# MCU.net
KiCad netlist of a schematic drawn in Altium Designer
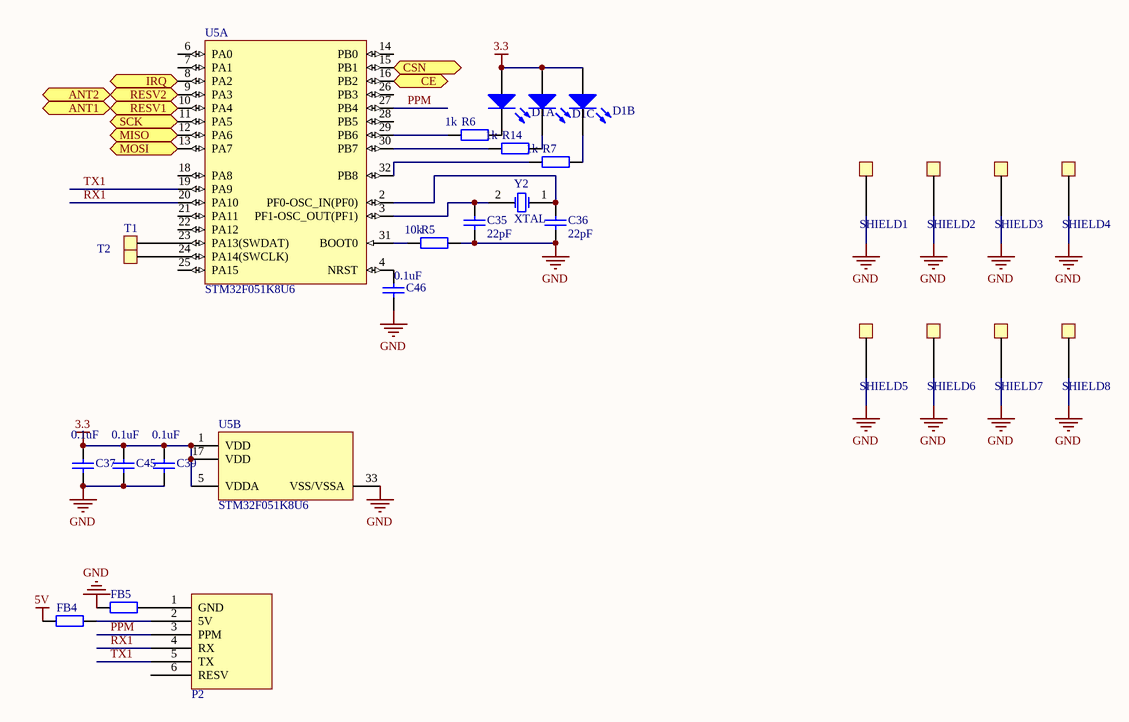
[diagram p0: MCU.SchDoc]

(export (version "E")
  (design (tool "Eeschema 10.0.6"))
  (components
    (comp (ref "C35")
      (value "22pF")
      (footprint "0402")
      (description "Capacitor")
      (fields (field (name "PUBLISHER") "Altium Limited"))
      (libsource (lib "RTC6705") (part "Cap"))
    )
    (comp (ref "C36")
      (value "22pF")
      (footprint "0402")
      (description "Capacitor")
      (fields (field (name "PUBLISHER") "Altium Limited"))
      (libsource (lib "RTC6705") (part "Cap"))
    )
    (comp (ref "C37")
      (value "0.1uF")
      (footprint "0402")
      (description "Capacitor")
      (fields (field (name "PUBLISHER") "Altium Limited"))
      (libsource (lib "RTC6705") (part "Cap"))
    )
    (comp (ref "C39")
      (value "0.1uF")
      (footprint "0402")
      (description "Capacitor")
      (fields (field (name "PUBLISHER") "Altium Limited"))
      (libsource (lib "RTC6705") (part "Cap"))
    )
    (comp (ref "C45")
      (value "0.1uF")
      (footprint "0402")
      (description "Capacitor")
      (fields (field (name "PUBLISHER") "Altium Limited"))
      (libsource (lib "RTC6705") (part "Cap"))
    )
    (comp (ref "C46")
      (value "0.1uF")
      (footprint "0402")
      (description "Capacitor")
      (fields (field (name "PUBLISHER") "Altium Limited"))
      (libsource (lib "RTC6705") (part "Cap"))
    )
    (comp (ref "D1")
      (value "LEDx3")
      (footprint "LC-0603_Rx2")
      (description "Typical RED GaAs LED")
      (fields (field (name "PUBLISHER") "Altium Limited"))
      (libsource (lib "sch") (part "LEDx3"))
    )
    (comp (ref "FB4")
      (value "Res2")
      (footprint "0402")
      (description "Resistor")
      (fields (field (name "PUBLISHER") "Altium Limited"))
      (libsource (lib "RTC6705") (part "Res2"))
    )
    (comp (ref "FB5")
      (value "Res2")
      (footprint "0402")
      (description "Resistor")
      (fields (field (name "PUBLISHER") "Altium Limited"))
      (libsource (lib "RTC6705") (part "Res2"))
    )
    (comp (ref "P2") (value "PPMInf") (footprint "PPMInf") (libsource (lib "NRF24L01_PA") (part "PPMInf")))
    (comp (ref "R5")
      (value "10k")
      (footprint "0402")
      (description "Resistor")
      (fields (field (name "PUBLISHER") "Altium Limited"))
      (libsource (lib "RTC6705") (part "Res2"))
    )
    (comp (ref "R6")
      (value "1k")
      (footprint "0402")
      (description "Resistor")
      (fields (field (name "PUBLISHER") "Altium Limited"))
      (libsource (lib "RTC6705") (part "Res2"))
    )
    (comp (ref "R7")
      (value "1k")
      (footprint "0402")
      (description "Resistor")
      (fields (field (name "PUBLISHER") "Altium Limited"))
      (libsource (lib "RTC6705") (part "Res2"))
    )
    (comp (ref "R14")
      (value "1k")
      (footprint "0402")
      (description "Resistor")
      (fields (field (name "PUBLISHER") "Altium Limited"))
      (libsource (lib "RTC6705") (part "Res2"))
    )
    (comp (ref "SHIELD1")
      (value "D")
      (footprint "ShieldHolder_6.5*0.8")
      (libsource (lib "") (part "TestPad_1"))
    )
    (comp (ref "SHIELD2")
      (value "D")
      (footprint "ShieldHolder_6.5*0.8")
      (libsource (lib "") (part "TestPad_1"))
    )
    (comp (ref "SHIELD3")
      (value "D")
      (footprint "ShieldHolder_6.5*0.8")
      (libsource (lib "") (part "TestPad_1"))
    )
    (comp (ref "SHIELD4")
      (value "D")
      (footprint "ShieldHolder_6.5*0.8")
      (libsource (lib "") (part "TestPad_1"))
    )
    (comp (ref "SHIELD5")
      (value "D")
      (footprint "ShieldHolder_6.5*0.8")
      (libsource (lib "") (part "TestPad_1"))
    )
    (comp (ref "SHIELD6")
      (value "D")
      (footprint "ShieldHolder_6.5*0.8")
      (libsource (lib "") (part "TestPad_1"))
    )
    (comp (ref "SHIELD7")
      (value "D")
      (footprint "ShieldHolder_6.5*0.8")
      (libsource (lib "") (part "TestPad_1"))
    )
    (comp (ref "SHIELD8")
      (value "D")
      (footprint "ShieldHolder_6.5*0.8")
      (libsource (lib "") (part "TestPad_1"))
    )
    (comp (ref "T1") (value "D") (footprint "TestPad - 1mm") (libsource (lib "sch") (part "TestPad")))
    (comp (ref "T2") (value "TestPad") (footprint "TestPad - 1mm") (libsource (lib "sch") (part "TestPad")))
    (comp (ref "U5")
      (value "STM32F051K8U6")
      (footprint "STM-UFQFPN32_NX")
      (libsource (lib "STMicroelectronics STM32 F0") (part "STM32F051K8U6"))
    )
    (comp (ref "Y2")
      (value "XTAL")
      (footprint "OSCILLATOR-3.2X2.5 - 2P")
      (description "Crystal Oscillator")
      (fields (field (name "PUBLISHER") "Altium Limited"))
      (libsource (lib "Miscellaneous Devices") (part "XTAL"))
    )
  )
  (nets
    (net (code "5") (name "/CE") (class "Default")
      (node (ref "U5") (pin "16") (pinfunction "PB2_16") (pintype "bidirectional"))
    )
    (net (code "6") (name "/CSN") (class "Default")
      (node (ref "U5") (pin "15") (pinfunction "PB1_15") (pintype "bidirectional"))
    )
    (net (code "7") (name "/IRQ") (class "Default")
      (node (ref "U5") (pin "8") (pinfunction "PA2_8") (pintype "bidirectional"))
    )
    (net (code "8") (name "/MISO") (class "Default")
      (node (ref "U5") (pin "12") (pinfunction "PA6_12") (pintype "bidirectional"))
    )
    (net (code "9") (name "/MOSI") (class "Default")
      (node (ref "U5") (pin "13") (pinfunction "PA7_13") (pintype "bidirectional"))
    )
    (net (code "10") (name "/PPM") (class "Default")
      (node (ref "P2") (pin "3") (pinfunction "PPM_3") (pintype "passive"))
      (node (ref "U5") (pin "27") (pinfunction "PB4_27") (pintype "bidirectional"))
    )
    (net (code "11") (name "/RESV1") (class "Default")
      (node (ref "U5") (pin "10") (pinfunction "PA4_10") (pintype "bidirectional"))
    )
    (net (code "12") (name "/RESV2") (class "Default")
      (node (ref "U5") (pin "9") (pinfunction "PA3_9") (pintype "bidirectional"))
    )
    (net (code "13") (name "/RX1") (class "Default")
      (node (ref "P2") (pin "4") (pinfunction "RX_4") (pintype "passive"))
      (node (ref "U5") (pin "20") (pinfunction "PA10_20") (pintype "bidirectional"))
    )
    (net (code "14") (name "/SCK") (class "Default")
      (node (ref "U5") (pin "11") (pinfunction "PA5_11") (pintype "bidirectional"))
    )
    (net (code "15") (name "/TX1") (class "Default")
      (node (ref "P2") (pin "5") (pinfunction "TX_5") (pintype "passive"))
      (node (ref "U5") (pin "19") (pinfunction "PA9_19") (pintype "bidirectional"))
    )
    (net (code "16") (name "3.3") (class "Default")
      (node (ref "C37") (pin "1") (pinfunction "1_1") (pintype "passive"))
      (node (ref "C39") (pin "1") (pinfunction "1_1") (pintype "passive"))
      (node (ref "C45") (pin "1") (pinfunction "1_1") (pintype "passive"))
      (node (ref "D1") (pin "2") (pinfunction "A_2") (pintype "passive"))
      (node (ref "U5") (pin "1") (pinfunction "VDD_1") (pintype "power_in"))
      (node (ref "U5") (pin "17") (pinfunction "VDD_17") (pintype "power_in"))
      (node (ref "U5") (pin "5") (pinfunction "VDDA_5") (pintype "power_in"))
    )
    (net (code "17") (name "5V") (class "Default")
      (node (ref "FB4") (pin "1") (pinfunction "1_1") (pintype "passive"))
    )
    (net (code "18") (name "GND") (class "Default")
      (node (ref "C35") (pin "2") (pinfunction "2_2") (pintype "passive"))
      (node (ref "C36") (pin "1") (pinfunction "1_1") (pintype "passive"))
      (node (ref "C37") (pin "2") (pinfunction "2_2") (pintype "passive"))
      (node (ref "C39") (pin "2") (pinfunction "2_2") (pintype "passive"))
      (node (ref "C45") (pin "2") (pinfunction "2_2") (pintype "passive"))
      (node (ref "C46") (pin "2") (pinfunction "2_2") (pintype "passive"))
      (node (ref "FB5") (pin "1") (pinfunction "1_1") (pintype "passive"))
      (node (ref "R5") (pin "2") (pinfunction "2_2") (pintype "passive"))
      (node (ref "SHIELD1") (pin "1") (pinfunction "3_1") (pintype "passive"))
      (node (ref "SHIELD2") (pin "1") (pinfunction "3_1") (pintype "passive"))
      (node (ref "SHIELD3") (pin "1") (pinfunction "3_1") (pintype "passive"))
      (node (ref "SHIELD4") (pin "1") (pinfunction "3_1") (pintype "passive"))
      (node (ref "SHIELD5") (pin "1") (pinfunction "3_1") (pintype "passive"))
      (node (ref "SHIELD6") (pin "1") (pinfunction "3_1") (pintype "passive"))
      (node (ref "SHIELD7") (pin "1") (pinfunction "3_1") (pintype "passive"))
      (node (ref "SHIELD8") (pin "1") (pinfunction "3_1") (pintype "passive"))
      (node (ref "U5") (pin "33") (pinfunction "VSS/VSSA_33") (pintype "power_in"))
    )
    (net (code "19") (name "Net-(D1A-K)") (class "Default")
      (node (ref "D1") (pin "1") (pinfunction "K_1") (pintype "passive"))
      (node (ref "R6") (pin "2") (pinfunction "2_2") (pintype "passive"))
    )
    (net (code "20") (name "Net-(D1B-K)") (class "Default")
      (node (ref "D1") (pin "3") (pinfunction "K_3") (pintype "passive"))
      (node (ref "R7") (pin "2") (pinfunction "2_2") (pintype "passive"))
    )
    (net (code "21") (name "Net-(D1C-K)") (class "Default")
      (node (ref "D1") (pin "4") (pinfunction "K_4") (pintype "passive"))
      (node (ref "R14") (pin "2") (pinfunction "2_2") (pintype "passive"))
    )
    (net (code "22") (name "Net-(P2-5V)") (class "Default")
      (node (ref "FB4") (pin "2") (pinfunction "2_2") (pintype "passive"))
      (node (ref "P2") (pin "2") (pinfunction "5V_2") (pintype "passive"))
    )
    (net (code "23") (name "Net-(P2-GND)") (class "Default")
      (node (ref "FB5") (pin "2") (pinfunction "2_2") (pintype "passive"))
      (node (ref "P2") (pin "1") (pinfunction "GND_1") (pintype "passive"))
    )
    (net (code "24") (name "Net-(T1-3)") (class "Default")
      (node (ref "T1") (pin "1") (pinfunction "3_1") (pintype "passive"))
      (node (ref "U5") (pin "23") (pinfunction "PA13(SWDAT)_23") (pintype "bidirectional"))
    )
    (net (code "25") (name "Net-(T2-3)") (class "Default")
      (node (ref "T2") (pin "1") (pinfunction "3_1") (pintype "passive"))
      (node (ref "U5") (pin "24") (pinfunction "PA14(SWCLK)_24") (pintype "bidirectional"))
    )
    (net (code "26") (name "Net-(U5A-BOOT0)") (class "Default")
      (node (ref "R5") (pin "1") (pinfunction "1_1") (pintype "passive"))
      (node (ref "U5") (pin "31") (pinfunction "BOOT0_31") (pintype "input"))
    )
    (net (code "27") (name "Net-(U5A-NRST)") (class "Default")
      (node (ref "C46") (pin "1") (pinfunction "1_1") (pintype "passive"))
      (node (ref "U5") (pin "4") (pinfunction "NRST_4") (pintype "bidirectional"))
    )
    (net (code "28") (name "Net-(U5A-PB6)") (class "Default")
      (node (ref "R6") (pin "1") (pinfunction "1_1") (pintype "passive"))
      (node (ref "U5") (pin "29") (pinfunction "PB6_29") (pintype "bidirectional"))
    )
    (net (code "29") (name "Net-(U5A-PB7)") (class "Default")
      (node (ref "R14") (pin "1") (pinfunction "1_1") (pintype "passive"))
      (node (ref "U5") (pin "30") (pinfunction "PB7_30") (pintype "bidirectional"))
    )
    (net (code "30") (name "Net-(U5A-PB8)") (class "Default")
      (node (ref "R7") (pin "1") (pinfunction "1_1") (pintype "passive"))
      (node (ref "U5") (pin "32") (pinfunction "PB8_32") (pintype "bidirectional"))
    )
    (net (code "31") (name "Net-(U5A-PF0-OSC_IN(PF0))") (class "Default")
      (node (ref "C36") (pin "2") (pinfunction "2_2") (pintype "passive"))
      (node (ref "U5") (pin "2") (pinfunction "PF0-OSC_IN(PF0)_2") (pintype "bidirectional"))
      (node (ref "Y2") (pin "1") (pinfunction "OSC1_1") (pintype "passive"))
    )
    (net (code "32") (name "Net-(U5A-PF1-OSC_OUT(PF1))") (class "Default")
      (node (ref "C35") (pin "1") (pinfunction "1_1") (pintype "passive"))
      (node (ref "U5") (pin "3") (pinfunction "PF1-OSC_OUT(PF1)_3") (pintype "bidirectional"))
      (node (ref "Y2") (pin "2") (pinfunction "OSC2_2") (pintype "passive"))
    )
    (net (code "33") (name "unconnected-(P2-RESV-Pad6)") (class "Default")
      (node (ref "P2") (pin "6") (pinfunction "RESV_6") (pintype "passive"))
    )
    (net (code "34") (name "unconnected-(U5A-PA0-Pad6)") (class "Default")
      (node (ref "U5") (pin "6") (pinfunction "PA0_6") (pintype "bidirectional"))
    )
    (net (code "35") (name "unconnected-(U5A-PA1-Pad7)") (class "Default")
      (node (ref "U5") (pin "7") (pinfunction "PA1_7") (pintype "bidirectional"))
    )
    (net (code "36") (name "unconnected-(U5A-PA8-Pad18)") (class "Default")
      (node (ref "U5") (pin "18") (pinfunction "PA8_18") (pintype "bidirectional"))
    )
    (net (code "37") (name "unconnected-(U5A-PA11-Pad21)") (class "Default")
      (node (ref "U5") (pin "21") (pinfunction "PA11_21") (pintype "bidirectional"))
    )
    (net (code "38") (name "unconnected-(U5A-PA12-Pad22)") (class "Default")
      (node (ref "U5") (pin "22") (pinfunction "PA12_22") (pintype "bidirectional"))
    )
    (net (code "39") (name "unconnected-(U5A-PA15-Pad25)") (class "Default")
      (node (ref "U5") (pin "25") (pinfunction "PA15_25") (pintype "bidirectional"))
    )
    (net (code "40") (name "unconnected-(U5A-PB0-Pad14)") (class "Default")
      (node (ref "U5") (pin "14") (pinfunction "PB0_14") (pintype "bidirectional"))
    )
    (net (code "41") (name "unconnected-(U5A-PB3-Pad26)") (class "Default")
      (node (ref "U5") (pin "26") (pinfunction "PB3_26") (pintype "bidirectional"))
    )
    (net (code "42") (name "unconnected-(U5A-PB5-Pad28)") (class "Default")
      (node (ref "U5") (pin "28") (pinfunction "PB5_28") (pintype "bidirectional"))
    )
  )
)
